# STB_FanControl.net
KiCad netlist of a schematic drawn in Altium Designer
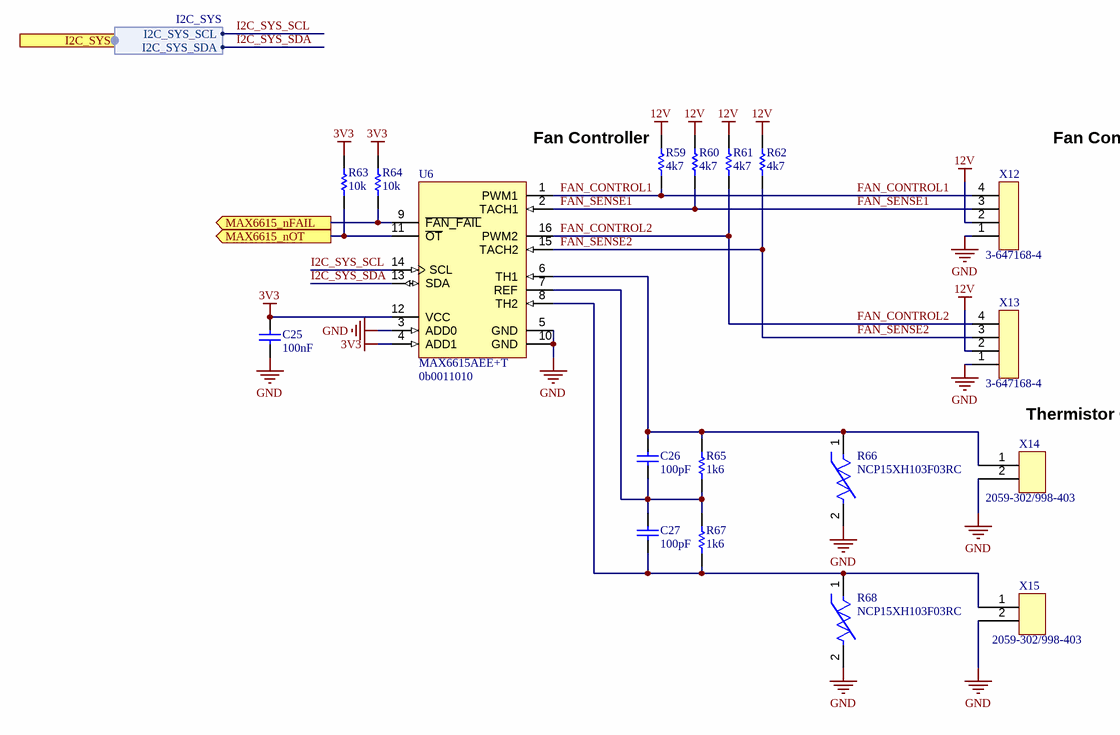
[diagram p0: STB_FanControl.SchDoc]

(export (version "E")
  (design (tool "Eeschema 10.0.6"))
  (components
    (comp (ref "C25")
      (value "100nF")
      (footprint "CAPC1050X55X23LL05T13")
      (description "Chip Capacitor, 100 nF, +/- 10%, 16 V, -55 to 125 degC, 0402 (1005 Metric), RoHS, Tape and Reel")
      (fields
        (field (name "MANUFACTURER") "Samsung Electro-Mechanics")
        (field (name "MANUFACTURER PART NUMBER") "CL05B104KO5NNNC")
      )
      (libsource (lib "Altium Content Vault") (part "CAP-NP-2"))
    )
    (comp (ref "C26")
      (value "100pF")
      (footprint "CAPC1005X56X25LL10T15")
      (fields
        (field (name "MANUFACTURER") "AVX Interconnect / Elco")
        (field (name "PART NUMBER") "04023A101KAT2A")
      )
      (libsource (lib "Altium Content Vault") (part "CAP"))
    )
    (comp (ref "C27")
      (value "100pF")
      (footprint "CAPC1005X56X25LL10T15")
      (fields
        (field (name "MANUFACTURER") "AVX Interconnect / Elco")
        (field (name "PART NUMBER") "04023A101KAT2A")
      )
      (libsource (lib "Altium Content Vault") (part "CAP"))
    )
    (comp (ref "R59")
      (value "4k7")
      (footprint "RESC1005X40X25LL05T10")
      (fields
        (field (name "MANUFACTURER") "Yageo / Phycomp")
        (field (name "PART NUMBER") "RC0402FR-074K7L")
        (field (name "TOLERANCE") "1%")
      )
      (libsource (lib "Altium Content Vault") (part "RES"))
    )
    (comp (ref "R60")
      (value "4k7")
      (footprint "RESC1005X40X25LL05T10")
      (fields
        (field (name "MANUFACTURER") "Yageo / Phycomp")
        (field (name "PART NUMBER") "RC0402FR-074K7L")
        (field (name "TOLERANCE") "1%")
      )
      (libsource (lib "Altium Content Vault") (part "RES"))
    )
    (comp (ref "R61")
      (value "4k7")
      (footprint "RESC1005X40X25LL05T10")
      (fields
        (field (name "MANUFACTURER") "Yageo / Phycomp")
        (field (name "PART NUMBER") "RC0402FR-074K7L")
        (field (name "TOLERANCE") "1%")
      )
      (libsource (lib "Altium Content Vault") (part "RES"))
    )
    (comp (ref "R62")
      (value "4k7")
      (footprint "RESC1005X40X25LL05T10")
      (fields
        (field (name "MANUFACTURER") "Yageo / Phycomp")
        (field (name "PART NUMBER") "RC0402FR-074K7L")
        (field (name "TOLERANCE") "1%")
      )
      (libsource (lib "Altium Content Vault") (part "RES"))
    )
    (comp (ref "R63")
      (value "10k")
      (footprint "RESC1005X40X25LL05T05")
      (description "Chip Resistor, 10 KOhm, +/- 1%, 0.1 W, -55 to 155 degC, 0402 (1005 Metric), RoHS, Tape and Reel")
      (fields (field (name "TOLERANCE") "1%") (field (name "MANUFACTURER") "Panasonic"))
      (libsource (lib "Altium Content Vault") (part "RES-2"))
    )
    (comp (ref "R64")
      (value "10k")
      (footprint "RESC1005X40X25LL05T05")
      (description "Chip Resistor, 10 KOhm, +/- 1%, 0.1 W, -55 to 155 degC, 0402 (1005 Metric), RoHS, Tape and Reel")
      (fields (field (name "TOLERANCE") "1%") (field (name "MANUFACTURER") "Panasonic"))
      (libsource (lib "Altium Content Vault") (part "RES-2"))
    )
    (comp (ref "R65")
      (value "1k6")
      (footprint "RESC1005X40X25LL05T10")
      (fields
        (field (name "MANUFACTURER") "Yageo / Phycomp")
        (field (name "PART NUMBER") "RC0402FR-071K6L")
        (field (name "TOLERANCE") "1%")
      )
      (libsource (lib "Altium Content Vault") (part "RES"))
    )
    (comp (ref "R66")
      (value "NCP15XH103F03RC")
      (footprint "FP-NCP15-NCU15-0_05-IPC_C")
      (description "NTC Thermistor for Temperature Sensor, 0402, 10kΩ, 1%, 0.1mA, 5V")
      (fields (field (name "TOLERANCE") "1%") (field (name "MANUFACTURER") "Murata"))
      (libsource (lib "Altium Content Vault") (part "3b148a6ebabc5fb4d708a66c052d352"))
    )
    (comp (ref "R67")
      (value "1k6")
      (footprint "RESC1005X40X25LL05T10")
      (fields
        (field (name "MANUFACTURER") "Yageo / Phycomp")
        (field (name "PART NUMBER") "RC0402FR-071K6L")
        (field (name "TOLERANCE") "1%")
      )
      (libsource (lib "Altium Content Vault") (part "RES"))
    )
    (comp (ref "R68")
      (value "NCP15XH103F03RC")
      (footprint "FP-NCP15-NCU15-0_05-IPC_C")
      (description "NTC Thermistor for Temperature Sensor, 0402, 10kΩ, 1%, 0.1mA, 5V")
      (fields (field (name "TOLERANCE") "1%") (field (name "MANUFACTURER") "Murata"))
      (libsource (lib "Altium Content Vault") (part "3b148a6ebabc5fb4d708a66c052d352"))
    )
    (comp (ref "U6")
      (value "MAX6615AEE+T")
      (footprint "MAXM-E16+1_M")
      (fields (field (name "GENERIC PART NUMBER") "MAX6615") (field (name "MANUFACTURER") "Maxim"))
      (libsource (lib "Altium Content Vault") (part "MAX6615-E16X1"))
    )
    (comp (ref "X12")
      (value "3-647168-4")
      (footprint "3-647168-4")
      (fields
        (field (name "MANUFACTURER") "TE Connectivity")
        (field (name "MANUFACTURER PART NUMBER") "3-647166-4")
      )
      (libsource (lib "STB_Schlib") (part "3-647168-4"))
    )
    (comp (ref "X13")
      (value "3-647168-4")
      (footprint "3-647168-4")
      (fields
        (field (name "MANUFACTURER") "TE Connectivity")
        (field (name "MANUFACTURER PART NUMBER") "3-647166-4")
      )
      (libsource (lib "STB_Schlib") (part "3-647168-4"))
    )
    (comp (ref "X14")
      (value "2059-302/998-403")
      (footprint "2059-302/998-403")
      (description "Barrier Strip Terminal Block, 3A, 0.34mm2, 1 Row(s), 1 Deck(s)")
      (fields (field (name "MANUFACTURER") "WAGO") (field (name "SAFETY APPROVAL") "UL"))
      (libsource (lib "STB_Schlib") (part "2059-302/998-403"))
    )
    (comp (ref "X15")
      (value "2059-302/998-403")
      (footprint "2059-302/998-403")
      (description "Barrier Strip Terminal Block, 3A, 0.34mm2, 1 Row(s), 1 Deck(s)")
      (fields (field (name "MANUFACTURER") "WAGO") (field (name "SAFETY APPROVAL") "UL"))
      (libsource (lib "STB_Schlib") (part "2059-302/998-403"))
    )
  )
  (nets
    (net (code "2") (name "/FAN_CONTROL1") (class "Default")
      (node (ref "R59") (pin "1") (pinfunction "1_1") (pintype "passive"))
      (node (ref "U6") (pin "1") (pinfunction "PWM1_1") (pintype "open_collector"))
      (node (ref "X12") (pin "4") (pintype "passive"))
    )
    (net (code "3") (name "/FAN_CONTROL2") (class "Default")
      (node (ref "R61") (pin "1") (pinfunction "1_1") (pintype "passive"))
      (node (ref "U6") (pin "16") (pinfunction "PWM2_16") (pintype "open_collector"))
      (node (ref "X13") (pin "4") (pintype "passive"))
    )
    (net (code "4") (name "/FAN_SENSE1") (class "Default")
      (node (ref "R60") (pin "1") (pinfunction "1_1") (pintype "passive"))
      (node (ref "U6") (pin "2") (pinfunction "TACH1_2") (pintype "input"))
      (node (ref "X12") (pin "3") (pintype "passive"))
    )
    (net (code "5") (name "/FAN_SENSE2") (class "Default")
      (node (ref "R62") (pin "1") (pinfunction "1_1") (pintype "passive"))
      (node (ref "U6") (pin "15") (pinfunction "TACH2_15") (pintype "input"))
      (node (ref "X13") (pin "3") (pintype "passive"))
    )
    (net (code "6") (name "/I2C_SYS_SCL") (class "Default")
      (node (ref "U6") (pin "14") (pinfunction "SCL_14") (pintype "input"))
    )
    (net (code "7") (name "/I2C_SYS_SDA") (class "Default")
      (node (ref "U6") (pin "13") (pinfunction "SDA_13") (pintype "bidirectional"))
    )
    (net (code "8") (name "/MAX6615_nFAIL") (class "Default")
      (node (ref "R64") (pin "1") (pinfunction "1_1") (pintype "passive"))
      (node (ref "U6") (pin "9") (pinfunction "~{FAN_FAIL}_9") (pintype "tri_state"))
    )
    (net (code "9") (name "/MAX6615_nOT") (class "Default")
      (node (ref "R63") (pin "1") (pinfunction "1_1") (pintype "passive"))
      (node (ref "U6") (pin "11") (pinfunction "~{OT}_11") (pintype "tri_state"))
    )
    (net (code "11") (name "3V3") (class "Default")
      (node (ref "C25") (pin "2") (pinfunction "2_2") (pintype "passive"))
      (node (ref "R63") (pin "2") (pinfunction "2_2") (pintype "passive"))
      (node (ref "R64") (pin "2") (pinfunction "2_2") (pintype "passive"))
      (node (ref "U6") (pin "12") (pinfunction "VCC_12") (pintype "power_in"))
      (node (ref "U6") (pin "4") (pinfunction "ADD1_4") (pintype "input"))
    )
    (net (code "12") (name "12V") (class "Default")
      (node (ref "R59") (pin "2") (pinfunction "2_2") (pintype "passive"))
      (node (ref "R60") (pin "2") (pinfunction "2_2") (pintype "passive"))
      (node (ref "R61") (pin "2") (pinfunction "2_2") (pintype "passive"))
      (node (ref "R62") (pin "2") (pinfunction "2_2") (pintype "passive"))
      (node (ref "X12") (pin "2") (pintype "passive"))
      (node (ref "X13") (pin "2") (pintype "passive"))
    )
    (net (code "13") (name "GND") (class "Default")
      (node (ref "C25") (pin "1") (pinfunction "1_1") (pintype "passive"))
      (node (ref "R66") (pin "2") (pinfunction "2_2") (pintype "passive"))
      (node (ref "R68") (pin "2") (pinfunction "2_2") (pintype "passive"))
      (node (ref "U6") (pin "10") (pinfunction "GND_10") (pintype "power_in"))
      (node (ref "U6") (pin "3") (pinfunction "ADD0_3") (pintype "input"))
      (node (ref "U6") (pin "5") (pinfunction "GND_5") (pintype "power_in"))
      (node (ref "X12") (pin "1") (pintype "passive"))
      (node (ref "X13") (pin "1") (pintype "passive"))
      (node (ref "X14") (pin "2") (pintype "passive"))
      (node (ref "X15") (pin "2") (pintype "passive"))
    )
    (net (code "14") (name "Net-(U6-REF)") (class "Default")
      (node (ref "C26") (pin "1") (pinfunction "1_1") (pintype "passive"))
      (node (ref "C27") (pin "2") (pinfunction "2_2") (pintype "passive"))
      (node (ref "R65") (pin "1") (pinfunction "1_1") (pintype "passive"))
      (node (ref "R67") (pin "2") (pinfunction "2_2") (pintype "passive"))
      (node (ref "U6") (pin "7") (pinfunction "REF_7") (pintype "tri_state"))
    )
    (net (code "15") (name "Net-(U6-TH1)") (class "Default")
      (node (ref "C26") (pin "2") (pinfunction "2_2") (pintype "passive"))
      (node (ref "R65") (pin "2") (pinfunction "2_2") (pintype "passive"))
      (node (ref "R66") (pin "1") (pinfunction "1_1") (pintype "passive"))
      (node (ref "U6") (pin "6") (pinfunction "TH1_6") (pintype "input"))
      (node (ref "X14") (pin "1") (pintype "passive"))
    )
    (net (code "16") (name "Net-(U6-TH2)") (class "Default")
      (node (ref "C27") (pin "1") (pinfunction "1_1") (pintype "passive"))
      (node (ref "R67") (pin "1") (pinfunction "1_1") (pintype "passive"))
      (node (ref "R68") (pin "1") (pinfunction "1_1") (pintype "passive"))
      (node (ref "U6") (pin "8") (pinfunction "TH2_8") (pintype "input"))
      (node (ref "X15") (pin "1") (pintype "passive"))
    )
  )
)
